# WeatherShield_Air.net
KiCad netlist of a schematic drawn in EAGLE
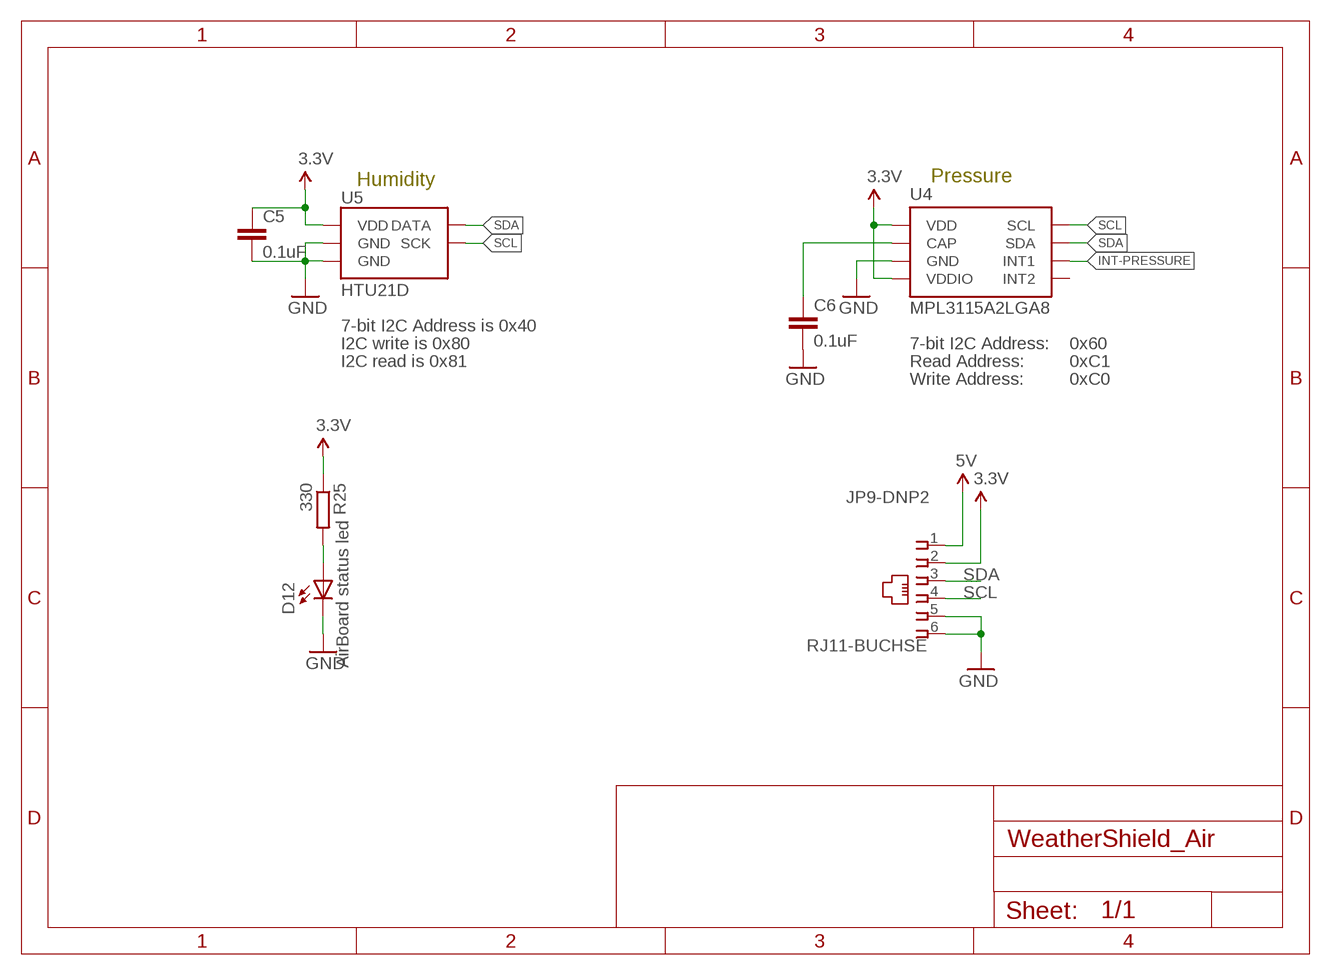
[diagram p0: schematic, sheet 1]

(export (version "E")
  (design (tool "Eeschema 10.0.6"))
  (components
    (comp (ref "C5")
      (value "0.1uF")
      (footprint "eagle-import:C0603")
      (libsource (lib "eagle-import") (part "C-EUC0603"))
    )
    (comp (ref "C6")
      (value "0.1uF")
      (footprint "eagle-import:C0603")
      (libsource (lib "eagle-import") (part "C-EUC0603"))
    )
    (comp (ref "D12")
      (value "AirBoard status led")
      (footprint "eagle-import:LED-0603")
      (libsource (lib "eagle-import") (part "LED0603"))
    )
    (comp (ref "JP9-DNP2")
      (value "RJ11-BUCHSE")
      (footprint "eagle-import:RJ11-STECKER")
      (libsource (lib "eagle-import") (part "RJ11-BUCHSE"))
    )
    (comp (ref "R25")
      (value "330")
      (footprint "eagle-import:R0603")
      (libsource (lib "eagle-import") (part "R-EU_R0603"))
    )
    (comp (ref "U4")
      (value "MPL3115A2LGA8")
      (footprint "eagle-import:LGA8")
      (libsource (lib "eagle-import") (part "MPL3115A2LGA8"))
    )
    (comp (ref "U5")
      (value "HTU21D")
      (footprint "eagle-import:HTU21D")
      (libsource (lib "eagle-import") (part "HTU21DSMD"))
    )
  )
  (nets
    (net (code "1") (name "3.3V") (class "Default")
      (node (ref "C5") (pin "1") (pinfunction "1_1") (pintype "passive"))
      (node (ref "JP9-DNP2") (pin "2") (pinfunction "2_2") (pintype "passive"))
      (node (ref "R25") (pin "1") (pinfunction "1_1") (pintype "passive"))
      (node (ref "U4") (pin "1") (pinfunction "VDD_1") (pintype "power_in"))
      (node (ref "U4") (pin "4") (pinfunction "VDDIO_4") (pintype "power_in"))
      (node (ref "U5") (pin "VDD") (pinfunction "VDD_VDD") (pintype "power_in"))
    )
    (net (code "2") (name "5V") (class "Default")
      (node (ref "JP9-DNP2") (pin "1") (pinfunction "1_1") (pintype "passive"))
    )
    (net (code "3") (name "GND") (class "Default")
      (node (ref "C5") (pin "2") (pinfunction "2_2") (pintype "passive"))
      (node (ref "C6") (pin "2") (pinfunction "2_2") (pintype "passive"))
      (node (ref "D12") (pin "C") (pinfunction "C_C") (pintype "passive"))
      (node (ref "JP9-DNP2") (pin "5") (pinfunction "5_5") (pintype "passive"))
      (node (ref "JP9-DNP2") (pin "6") (pinfunction "6_6") (pintype "passive"))
      (node (ref "U4") (pin "3") (pinfunction "GND_3") (pintype "power_in"))
      (node (ref "U5") (pin "7") (pinfunction "GND_7") (pintype "power_in"))
      (node (ref "U5") (pin "GND") (pinfunction "GND_GND") (pintype "power_in"))
    )
    (net (code "4") (name "INT-PRESSURE") (class "Default")
      (node (ref "U4") (pin "6") (pinfunction "INT1_6") (pintype "output"))
    )
    (net (code "5") (name "Net-(D12-PadA)") (class "Default")
      (node (ref "D12") (pin "A") (pinfunction "A_A") (pintype "passive"))
      (node (ref "R25") (pin "2") (pinfunction "2_2") (pintype "passive"))
    )
    (net (code "6") (name "Net-(U4-CAP)") (class "Default")
      (node (ref "C6") (pin "1") (pinfunction "1_1") (pintype "passive"))
      (node (ref "U4") (pin "2") (pinfunction "CAP_2") (pintype "power_in"))
    )
    (net (code "7") (name "SCL") (class "Default")
      (node (ref "JP9-DNP2") (pin "4") (pinfunction "4_4") (pintype "passive"))
      (node (ref "U4") (pin "8") (pinfunction "SCL_8") (pintype "bidirectional"))
      (node (ref "U5") (pin "SCK") (pinfunction "SCK_SCK") (pintype "input"))
    )
    (net (code "8") (name "SDA") (class "Default")
      (node (ref "JP9-DNP2") (pin "3") (pinfunction "3_3") (pintype "passive"))
      (node (ref "U4") (pin "7") (pinfunction "SDA_7") (pintype "bidirectional"))
      (node (ref "U5") (pin "DATA") (pinfunction "DATA_DATA") (pintype "bidirectional"))
    )
    (net (code "9") (name "unconnected-(U4-INT2-Pad5)") (class "Default")
      (node (ref "U4") (pin "5") (pinfunction "INT2_5") (pintype "output"))
    )
  )
)
